# CONVERTER_ALTIUM.net
KiCad netlist of a schematic drawn in Altium Designer
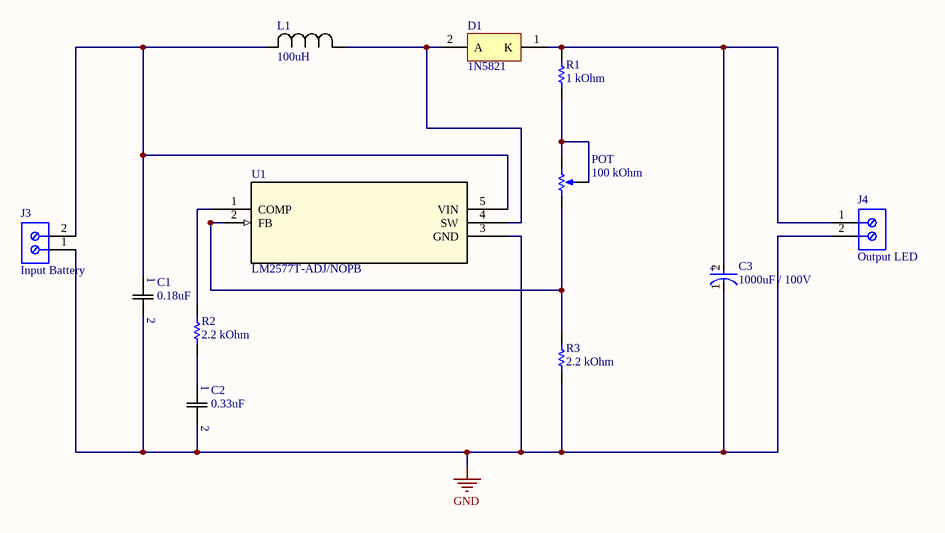
[diagram p0: CONVERTER_ALTIUM.SchDoc]

(export (version "E")
  (design (tool "Eeschema 10.0.6"))
  (components
    (comp (ref "C1")
      (value "0.18uF")
      (footprint "CAP_C322C_MR_X7R_KEM")
      (description "No Description Available")
      (fields
        (field (name "MANUFACTURER_PART_NUMBER") "C322C184K5R5TA")
        (field (name "COPYRIGHT") "Copyright (C) 2022 Ultra Librarian. All rights reserved.")
      )
      (libsource (lib "C322C184K5R5TA") (part "C322C184K5R5TA"))
    )
    (comp (ref "C2")
      (value "0.33uF")
      (footprint "CAP_C330_MR_X7R_KEM")
      (description "No Description Available")
      (fields
        (field (name "MANUFACTURER_PART_NUMBER") "C330C334K5R5TA")
        (field (name "COPYRIGHT") "Copyright (C) 2022 Ultra Librarian. All rights reserved.")
      )
      (libsource (lib "33Cap") (part "0.33uF Cap"))
    )
    (comp (ref "C3")
      (value "1000uF / 100V")
      (footprint "FP-RAD-TH-D_16_0_5-L_25_2-MFG")
      (description "Aluminum Electrolytic Capacitors (Radial Lead Type) 1000uF ±20% 50V")
      (fields (field (name "TOLERANCE") "20%"))
      (libsource (lib "Altium Content Vault") (part "203bc49f2ac43e59fd269a8c329ed05"))
    )
    (comp (ref "D1")
      (value "1N5821")
      (footprint "ONSC-AXIAL_LEAD-2-267-05_V")
      (description "Rectifier, 2-Pin Axial_Lead, Bulk Bag")
      (fields (field (name "MANUFACTURER") "On Semiconductor"))
      (libsource (lib "Altium Content Vault") (part "ONSC-D-K1A2-2_A"))
    )
    (comp (ref "J3")
      (value "Input Battery")
      (footprint "691102710002")
      (description "Series 102 - 5.00 mm Horizontal Entry Modular with Pressure Clamp WR-TBL, 2 pin")
      (fields
        (field (name "MANUFACTURER") "Wurth Elektronik")
        (field (name "PART NUMBER") "691102710002")
        (field (name "PUBLISHER") "WurthElektronik")
      )
      (libsource (lib "Altium Content Vault") (part "WE-CN-1P-F-TB2"))
    )
    (comp (ref "J4")
      (value "Output LED")
      (footprint "691102710002")
      (description "Series 102 - 5.00 mm Horizontal Entry Modular with Pressure Clamp WR-TBL, 2 pin")
      (fields
        (field (name "MANUFACTURER") "Wurth Elektronik")
        (field (name "PART NUMBER") "691102710002")
        (field (name "PUBLISHER") "WurthElektronik")
      )
      (libsource (lib "Altium Content Vault") (part "WE-CN-1P-F-TB2"))
    )
    (comp (ref "L1")
      (value "100uH")
      (footprint "IND_PE-53115NL_PUL")
      (description "No Description Available")
      (fields
        (field (name "MANUFACTURER_PART_NUMBER") "PE-53115NL")
        (field (name "COPYRIGHT") "Copyright (C) 2022 Ultra Librarian. All rights reserved.")
      )
      (libsource (lib "Inductor") (part "PE-53115NL"))
    )
    (comp (ref "POT")
      (value "100 kOhm")
      (footprint "BOUR-3362P")
      (description "Square Trimpot(R) Trimming Potentiometer, 10 KOhm, 300 V, -55 to 125 degC, 3-Pin THD, RoHS, Tube")
      (fields (field (name "TOLERANCE") "1%"))
      (libsource (lib "Altium Content Vault") (part "RES-POT-3"))
    )
    (comp (ref "R1")
      (value "1 kOhm")
      (footprint "RESA60-630X240")
      (description "Axial Resistor, 1 KOhm, +/- 1%, 250 mW, -55 to 155 degC, 2-Pin THD, RoHS, Bulk")
      (fields (field (name "TOLERANCE") "1%"))
      (libsource (lib "Altium Content Vault") (part "RES-2"))
    )
    (comp (ref "R2")
      (value "2.2 kOhm")
      (footprint "RESA60-630X240")
      (description "Axial Resistor, 1 KOhm, +/- 1%, 250 mW, -55 to 155 degC, 2-Pin THD, RoHS, Bulk")
      (fields (field (name "TOLERANCE") "1%"))
      (libsource (lib "Altium Content Vault") (part "RES-2"))
    )
    (comp (ref "R3")
      (value "2.2 kOhm")
      (footprint "RESA60-630X240")
      (description "Axial Resistor, 1 KOhm, +/- 1%, 250 mW, -55 to 155 degC, 2-Pin THD, RoHS, Bulk")
      (fields (field (name "TOLERANCE") "1%"))
      (libsource (lib "Altium Content Vault") (part "RES-2"))
    )
    (comp (ref "U1")
      (value "LM2577T-ADJ/NOPB")
      (footprint "T05A_TEX")
      (description "No Description Available")
      (fields (field (name "COPYRIGHT") "Copyright (C) 2022 Ultra Librarian. All rights reserved."))
      (libsource (lib "LM2577T-ADJ&slash_NOPB") (part "LM2577T-ADJ/NOPB"))
    )
  )
  (nets
    (net (code "1") (name "GND") (class "Default")
      (node (ref "C1") (pin "2") (pinfunction "2_2") (pintype "passive"))
      (node (ref "C2") (pin "2") (pinfunction "2_2") (pintype "passive"))
      (node (ref "C3") (pin "1") (pinfunction "C_1") (pintype "passive"))
      (node (ref "J3") (pin "1") (pinfunction "1_1") (pintype "passive"))
      (node (ref "J4") (pin "2") (pinfunction "2_2") (pintype "passive"))
      (node (ref "R3") (pin "1") (pinfunction "1_1") (pintype "passive"))
      (node (ref "U1") (pin "3") (pinfunction "GND_3") (pintype "power_in"))
    )
    (net (code "2") (name "Net-(C2-Pad1)") (class "Default")
      (node (ref "C2") (pin "1") (pinfunction "1_1") (pintype "passive"))
      (node (ref "R2") (pin "1") (pinfunction "1_1") (pintype "passive"))
    )
    (net (code "3") (name "Net-(C3-A)") (class "Default")
      (node (ref "C3") (pin "2") (pinfunction "A_2") (pintype "passive"))
      (node (ref "D1") (pin "1") (pinfunction "K_1") (pintype "passive"))
      (node (ref "J4") (pin "1") (pinfunction "1_1") (pintype "passive"))
      (node (ref "R1") (pin "2") (pinfunction "2_2") (pintype "passive"))
    )
    (net (code "4") (name "Net-(D1-A)") (class "Default")
      (node (ref "D1") (pin "2") (pinfunction "A_2") (pintype "passive"))
      (node (ref "L1") (pin "1") (pinfunction "1_1") (pintype "passive"))
      (node (ref "U1") (pin "4") (pinfunction "SW_4") (pintype "power_in"))
    )
    (net (code "5") (name "Net-(POT-CCW)") (class "Default")
      (node (ref "POT") (pin "1") (pinfunction "CCW_1") (pintype "passive"))
      (node (ref "R3") (pin "2") (pinfunction "2_2") (pintype "passive"))
      (node (ref "U1") (pin "2") (pinfunction "FB_2") (pintype "input"))
    )
    (net (code "6") (name "Net-(POT-CW)") (class "Default")
      (node (ref "POT") (pin "2") (pinfunction "S_2") (pintype "passive"))
      (node (ref "POT") (pin "3") (pinfunction "CW_3") (pintype "passive"))
      (node (ref "R1") (pin "1") (pinfunction "1_1") (pintype "passive"))
    )
    (net (code "7") (name "Net-(U1-COMP)") (class "Default")
      (node (ref "R2") (pin "2") (pinfunction "2_2") (pintype "passive"))
      (node (ref "U1") (pin "1") (pinfunction "COMP_1") (pintype "passive"))
    )
    (net (code "8") (name "Net-(U1-VIN)") (class "Default")
      (node (ref "C1") (pin "1") (pinfunction "1_1") (pintype "passive"))
      (node (ref "J3") (pin "2") (pinfunction "2_2") (pintype "passive"))
      (node (ref "L1") (pin "2") (pinfunction "2_2") (pintype "passive"))
      (node (ref "U1") (pin "5") (pinfunction "VIN_5") (pintype "power_in"))
    )
  )
)
